# 5_-USB2_TYPEC_USIC.net
KiCad netlist of a schematic drawn in Altium Designer
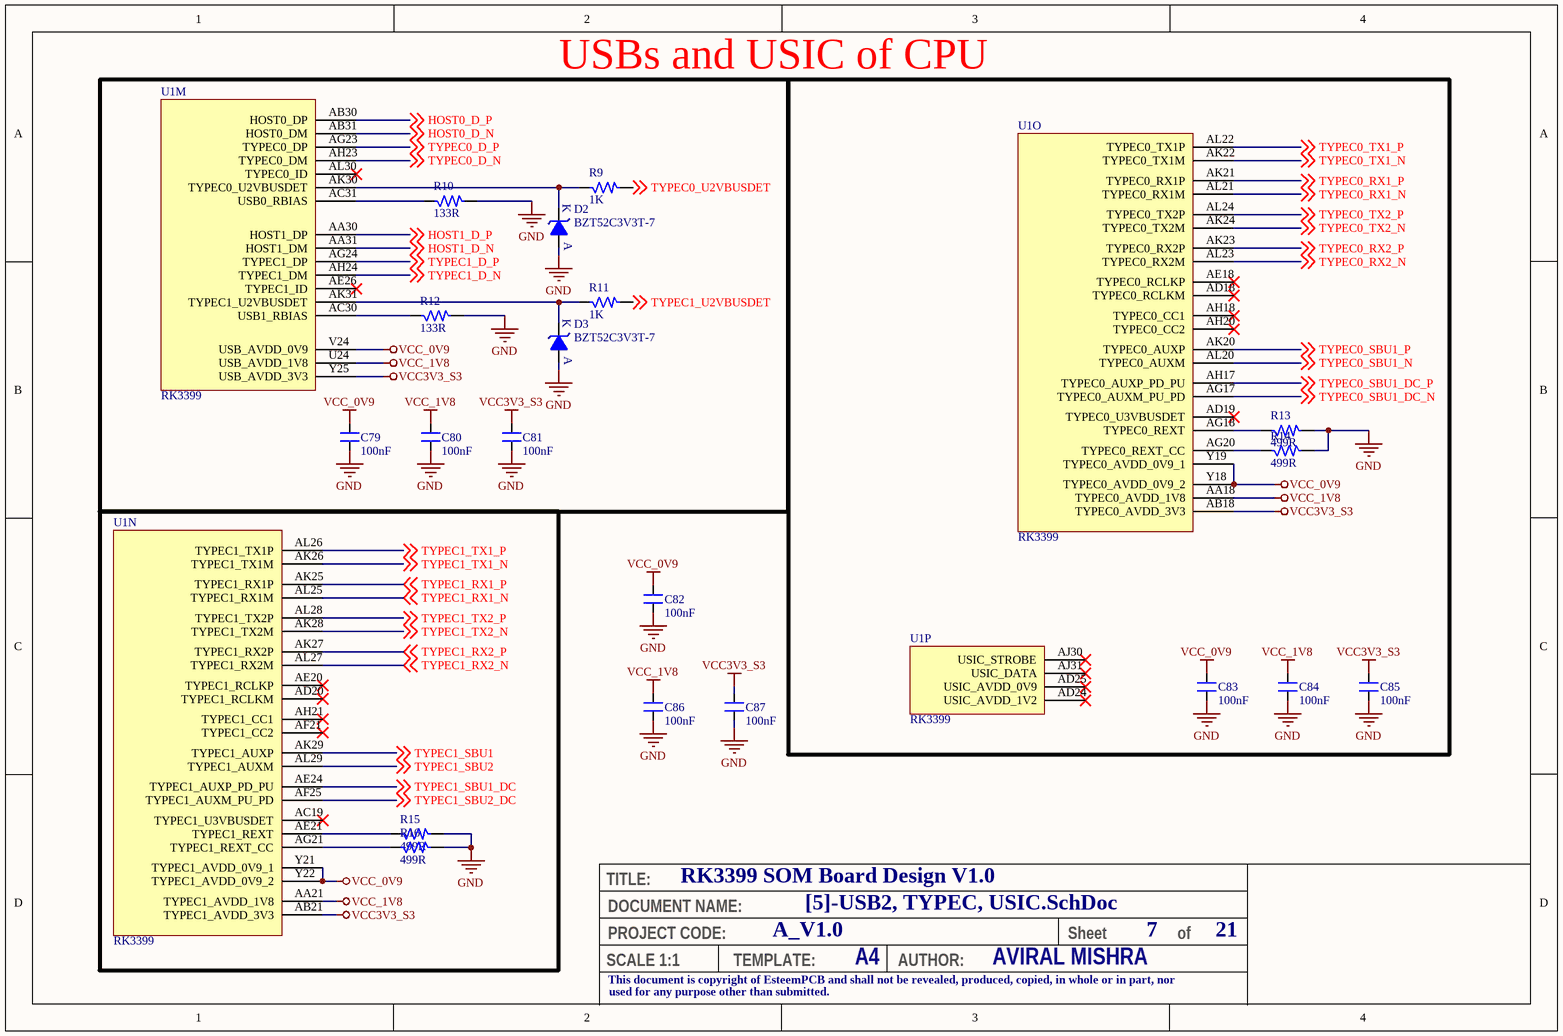
[diagram p0: [5]-USB2, TYPEC, USIC.SchDoc]

(export (version "E")
  (design (tool "Eeschema 10.0.6"))
  (components
    (comp (ref "C79")
      (value "100nF")
      (footprint "CAP_0201")
      (description "0.1µF ±10% 25V Ceramic Capacitor X5R 0201 (0603 Metric)")
      (fields
        (field (name "MANUFACTURER") "TDK Corporation")
        (field (name "MANUFACTURER PART NUMBER") "C0603X5R1E104K030BB")
      )
      (libsource (lib "RK3399 _Module_Intlib") (part "CAP_100nF-25V-10%-0201"))
    )
    (comp (ref "C80")
      (value "100nF")
      (footprint "CAP_0201")
      (description "0.1µF ±10% 25V Ceramic Capacitor X5R 0201 (0603 Metric)")
      (fields
        (field (name "MANUFACTURER") "TDK Corporation")
        (field (name "MANUFACTURER PART NUMBER") "C0603X5R1E104K030BB")
      )
      (libsource (lib "RK3399 _Module_Intlib") (part "CAP_100nF-25V-10%-0201"))
    )
    (comp (ref "C81")
      (value "100nF")
      (footprint "CAP_0201")
      (description "0.1µF ±10% 25V Ceramic Capacitor X5R 0201 (0603 Metric)")
      (fields
        (field (name "MANUFACTURER") "TDK Corporation")
        (field (name "MANUFACTURER PART NUMBER") "C0603X5R1E104K030BB")
      )
      (libsource (lib "RK3399 _Module_Intlib") (part "CAP_100nF-25V-10%-0201"))
    )
    (comp (ref "C82")
      (value "100nF")
      (footprint "CAP_0201")
      (description "0.1µF ±10% 25V Ceramic Capacitor X5R 0201 (0603 Metric)")
      (fields
        (field (name "MANUFACTURER") "TDK Corporation")
        (field (name "MANUFACTURER PART NUMBER") "C0603X5R1E104K030BB")
      )
      (libsource (lib "RK3399 _Module_Intlib") (part "CAP_100nF-25V-10%-0201"))
    )
    (comp (ref "C83")
      (value "100nF")
      (footprint "CAP_0201")
      (description "0.1µF ±10% 25V Ceramic Capacitor X5R 0201 (0603 Metric)")
      (fields
        (field (name "MANUFACTURER") "TDK Corporation")
        (field (name "MANUFACTURER PART NUMBER") "C0603X5R1E104K030BB")
      )
      (libsource (lib "RK3399 _Module_Intlib") (part "CAP_100nF-25V-10%-0201"))
    )
    (comp (ref "C84")
      (value "100nF")
      (footprint "CAP_0201")
      (description "0.1µF ±10% 25V Ceramic Capacitor X5R 0201 (0603 Metric)")
      (fields
        (field (name "MANUFACTURER") "TDK Corporation")
        (field (name "MANUFACTURER PART NUMBER") "C0603X5R1E104K030BB")
      )
      (libsource (lib "RK3399 _Module_Intlib") (part "CAP_100nF-25V-10%-0201"))
    )
    (comp (ref "C85")
      (value "100nF")
      (footprint "CAP_0201")
      (description "0.1µF ±10% 25V Ceramic Capacitor X5R 0201 (0603 Metric)")
      (fields
        (field (name "MANUFACTURER") "TDK Corporation")
        (field (name "MANUFACTURER PART NUMBER") "C0603X5R1E104K030BB")
      )
      (libsource (lib "RK3399 _Module_Intlib") (part "CAP_100nF-25V-10%-0201"))
    )
    (comp (ref "C86")
      (value "100nF")
      (footprint "CAP_0201")
      (description "0.1µF ±10% 25V Ceramic Capacitor X5R 0201 (0603 Metric)")
      (fields
        (field (name "MANUFACTURER") "TDK Corporation")
        (field (name "MANUFACTURER PART NUMBER") "C0603X5R1E104K030BB")
      )
      (libsource (lib "RK3399 _Module_Intlib") (part "CAP_100nF-25V-10%-0201"))
    )
    (comp (ref "C87")
      (value "100nF")
      (footprint "CAP_0201")
      (description "0.1µF ±10% 25V Ceramic Capacitor X5R 0201 (0603 Metric)")
      (fields
        (field (name "MANUFACTURER") "TDK Corporation")
        (field (name "MANUFACTURER PART NUMBER") "C0603X5R1E104K030BB")
      )
      (libsource (lib "RK3399 _Module_Intlib") (part "CAP_100nF-25V-10%-0201"))
    )
    (comp (ref "D2")
      (value "BZT52C3V3T-7")
      (footprint "DIO_SOD523")
      (description "Zener Diode 3.3V 300mW ±6% Surface Mount SOD-523")
      (fields (field (name "MANUFACTURER") "Diodes Incorporated"))
      (libsource (lib "RK3399 _Module_Schlib") (part "DIO-Z_3.3V-300mW-SOD-523"))
    )
    (comp (ref "D3")
      (value "BZT52C3V3T-7")
      (footprint "DIO_SOD523")
      (description "Zener Diode 3.3V 300mW ±6% Surface Mount SOD-523")
      (fields (field (name "MANUFACTURER") "Diodes Incorporated"))
      (libsource (lib "RK3399 _Module_Schlib") (part "DIO-Z_3.3V-300mW-SOD-523"))
    )
    (comp (ref "R9")
      (value "1K")
      (footprint "RES_0201")
      (description "1 kOhms ±1% 0.05W, 1/20W Chip Resistor 0201 (0603 Metric) Thick Film")
      (fields
        (field (name "MANUFACTURER") "Yageo")
        (field (name "MANUFACTURER PART NUMBER") "RC0201FR-071KL")
      )
      (libsource (lib "RK3399 _Module_Intlib") (part "RES_1K-0.05W-1%-0201"))
    )
    (comp (ref "R10")
      (value "133R")
      (footprint "RES_0201")
      (description "133 Ohms ±1% 0.05W, 1/20W Chip Resistor 0201 (0603 Metric) Automotive AEC-Q200 Thick Film")
      (fields
        (field (name "MANUFACTURER") "Panasonic Electronic Components")
        (field (name "MANUFACTURER PART NUMBER") "ERJ-1GNF1330C")
      )
      (libsource (lib "RK3399 _Module_Intlib") (part "RES_133R-0.05W-1%-0201"))
    )
    (comp (ref "R11")
      (value "1K")
      (footprint "RES_0201")
      (description "1 kOhms ±1% 0.05W, 1/20W Chip Resistor 0201 (0603 Metric) Thick Film")
      (fields
        (field (name "MANUFACTURER") "Yageo")
        (field (name "MANUFACTURER PART NUMBER") "RC0201FR-071KL")
      )
      (libsource (lib "RK3399 _Module_Intlib") (part "RES_1K-0.05W-1%-0201"))
    )
    (comp (ref "R12")
      (value "133R")
      (footprint "RES_0201")
      (description "133 Ohms ±1% 0.05W, 1/20W Chip Resistor 0201 (0603 Metric) Automotive AEC-Q200 Thick Film")
      (fields
        (field (name "MANUFACTURER") "Panasonic Electronic Components")
        (field (name "MANUFACTURER PART NUMBER") "ERJ-1GNF1330C")
      )
      (libsource (lib "RK3399 _Module_Intlib") (part "RES_133R-0.05W-1%-0201"))
    )
    (comp (ref "R13")
      (value "499R")
      (footprint "RES_0201")
      (description "499 Ohms ±1% 0.05W, 1/20W Chip Resistor 0201 (0603 Metric) Thick Film")
      (fields
        (field (name "MANUFACTURER") "Stackpole Electronics Inc")
        (field (name "MANUFACTURER PART NUMBER") "RMCF0201FT499R")
      )
      (libsource (lib "RK3399 _Module_Intlib") (part "RES_499R-0.05W-1%-0201"))
    )
    (comp (ref "R14")
      (value "499R")
      (footprint "RES_0201")
      (description "499 Ohms ±1% 0.05W, 1/20W Chip Resistor 0201 (0603 Metric) Thick Film")
      (fields
        (field (name "MANUFACTURER") "Stackpole Electronics Inc")
        (field (name "MANUFACTURER PART NUMBER") "RMCF0201FT499R")
      )
      (libsource (lib "RK3399 _Module_Intlib") (part "RES_499R-0.05W-1%-0201"))
    )
    (comp (ref "R15")
      (value "499R")
      (footprint "RES_0201")
      (description "499 Ohms ±1% 0.05W, 1/20W Chip Resistor 0201 (0603 Metric) Thick Film")
      (fields
        (field (name "MANUFACTURER") "Stackpole Electronics Inc")
        (field (name "MANUFACTURER PART NUMBER") "RMCF0201FT499R")
      )
      (libsource (lib "RK3399 _Module_Intlib") (part "RES_499R-0.05W-1%-0201"))
    )
    (comp (ref "R16")
      (value "499R")
      (footprint "RES_0201")
      (description "499 Ohms ±1% 0.05W, 1/20W Chip Resistor 0201 (0603 Metric) Thick Film")
      (fields
        (field (name "MANUFACTURER") "Stackpole Electronics Inc")
        (field (name "MANUFACTURER PART NUMBER") "RMCF0201FT499R")
      )
      (libsource (lib "RK3399 _Module_Intlib") (part "RES_499R-0.05W-1%-0201"))
    )
    (comp (ref "U1")
      (value "RK3399")
      (footprint "FBGA828_23_826X826")
      (description "RK3399 is a low power, high performance processor for computing, personal mobile.")
      (fields (field (name "MANUFACTURER") "Rockchip"))
      (libsource (lib "RK3399 _Module_Schlib") (part "IC_RK3399-FCBGA828"))
    )
  )
  (nets
    (net (code "1") (name "GND") (class "Default")
      (node (ref "C79") (pin "2") (pinfunction "2_2") (pintype "passive"))
      (node (ref "C80") (pin "1") (pinfunction "1_1") (pintype "passive"))
      (node (ref "C81") (pin "1") (pinfunction "1_1") (pintype "passive"))
      (node (ref "C82") (pin "1") (pinfunction "1_1") (pintype "passive"))
      (node (ref "C83") (pin "1") (pinfunction "1_1") (pintype "passive"))
      (node (ref "C84") (pin "1") (pinfunction "1_1") (pintype "passive"))
      (node (ref "C85") (pin "1") (pinfunction "1_1") (pintype "passive"))
      (node (ref "C86") (pin "1") (pinfunction "1_1") (pintype "passive"))
      (node (ref "C87") (pin "1") (pinfunction "1_1") (pintype "passive"))
      (node (ref "D2") (pin "A") (pinfunction "A_A") (pintype "passive"))
      (node (ref "D3") (pin "A") (pinfunction "A_A") (pintype "passive"))
      (node (ref "R10") (pin "2") (pinfunction "2_2") (pintype "passive"))
      (node (ref "R12") (pin "2") (pinfunction "2_2") (pintype "passive"))
      (node (ref "R13") (pin "2") (pinfunction "2_2") (pintype "passive"))
      (node (ref "R14") (pin "2") (pinfunction "2_2") (pintype "passive"))
      (node (ref "R15") (pin "2") (pinfunction "2_2") (pintype "passive"))
      (node (ref "R16") (pin "2") (pinfunction "2_2") (pintype "passive"))
    )
    (net (code "2") (name "HOST0_D_N") (class "Default")
      (node (ref "U1") (pin "AB31") (pinfunction "HOST0_DM_AB31") (pintype "passive"))
    )
    (net (code "3") (name "HOST0_D_P") (class "Default")
      (node (ref "U1") (pin "AB30") (pinfunction "HOST0_DP_AB30") (pintype "passive"))
    )
    (net (code "4") (name "HOST1_D_N") (class "Default")
      (node (ref "U1") (pin "AA31") (pinfunction "HOST1_DM_AA31") (pintype "passive"))
    )
    (net (code "5") (name "HOST1_D_P") (class "Default")
      (node (ref "U1") (pin "AA30") (pinfunction "HOST1_DP_AA30") (pintype "passive"))
    )
    (net (code "6") (name "Net-(U1M-TYPEC0_U2VBUSDET)") (class "Default")
      (node (ref "D2") (pin "K") (pinfunction "K_K") (pintype "passive"))
      (node (ref "R9") (pin "1") (pinfunction "1_1") (pintype "passive"))
      (node (ref "U1") (pin "AK30") (pinfunction "TYPEC0_U2VBUSDET_AK30") (pintype "passive"))
    )
    (net (code "7") (name "Net-(U1M-TYPEC1_U2VBUSDET)") (class "Default")
      (node (ref "D3") (pin "K") (pinfunction "K_K") (pintype "passive"))
      (node (ref "R11") (pin "1") (pinfunction "1_1") (pintype "passive"))
      (node (ref "U1") (pin "AK31") (pinfunction "TYPEC1_U2VBUSDET_AK31") (pintype "passive"))
    )
    (net (code "8") (name "Net-(U1M-USB0_RBIAS)") (class "Default")
      (node (ref "R10") (pin "1") (pinfunction "1_1") (pintype "passive"))
      (node (ref "U1") (pin "AC31") (pinfunction "USB0_RBIAS_AC31") (pintype "passive"))
    )
    (net (code "9") (name "Net-(U1M-USB1_RBIAS)") (class "Default")
      (node (ref "R12") (pin "1") (pinfunction "1_1") (pintype "passive"))
      (node (ref "U1") (pin "AC30") (pinfunction "USB1_RBIAS_AC30") (pintype "passive"))
    )
    (net (code "10") (name "Net-(U1N-TYPEC1_REXT)") (class "Default")
      (node (ref "R15") (pin "1") (pinfunction "1_1") (pintype "passive"))
      (node (ref "U1") (pin "AE21") (pinfunction "TYPEC1_REXT_AE21") (pintype "passive"))
    )
    (net (code "11") (name "Net-(U1N-TYPEC1_REXT_CC)") (class "Default")
      (node (ref "R16") (pin "1") (pinfunction "1_1") (pintype "passive"))
      (node (ref "U1") (pin "AG21") (pinfunction "TYPEC1_REXT_CC_AG21") (pintype "passive"))
    )
    (net (code "12") (name "Net-(U1O-TYPEC0_REXT)") (class "Default")
      (node (ref "R13") (pin "1") (pinfunction "1_1") (pintype "passive"))
      (node (ref "U1") (pin "AG18") (pinfunction "TYPEC0_REXT_AG18") (pintype "passive"))
    )
    (net (code "13") (name "Net-(U1O-TYPEC0_REXT_CC)") (class "Default")
      (node (ref "R14") (pin "1") (pinfunction "1_1") (pintype "passive"))
      (node (ref "U1") (pin "AG20") (pinfunction "TYPEC0_REXT_CC_AG20") (pintype "passive"))
    )
    (net (code "14") (name "TYPEC0_D_N") (class "Default")
      (node (ref "U1") (pin "AH23") (pinfunction "TYPEC0_DM_AH23") (pintype "passive"))
    )
    (net (code "15") (name "TYPEC0_D_P") (class "Default")
      (node (ref "U1") (pin "AG23") (pinfunction "TYPEC0_DP_AG23") (pintype "passive"))
    )
    (net (code "16") (name "TYPEC0_RX1_N") (class "Default")
      (node (ref "U1") (pin "AL21") (pinfunction "TYPEC0_RX1M_AL21") (pintype "passive"))
    )
    (net (code "17") (name "TYPEC0_RX1_P") (class "Default")
      (node (ref "U1") (pin "AK21") (pinfunction "TYPEC0_RX1P_AK21") (pintype "passive"))
    )
    (net (code "18") (name "TYPEC0_RX2_N") (class "Default")
      (node (ref "U1") (pin "AL23") (pinfunction "TYPEC0_RX2M_AL23") (pintype "passive"))
    )
    (net (code "19") (name "TYPEC0_RX2_P") (class "Default")
      (node (ref "U1") (pin "AK23") (pinfunction "TYPEC0_RX2P_AK23") (pintype "passive"))
    )
    (net (code "20") (name "TYPEC0_SBU1_DC_N") (class "Default")
      (node (ref "U1") (pin "AG17") (pinfunction "TYPEC0_AUXM_PU_PD_AG17") (pintype "passive"))
    )
    (net (code "21") (name "TYPEC0_SBU1_DC_P") (class "Default")
      (node (ref "U1") (pin "AH17") (pinfunction "TYPEC0_AUXP_PD_PU_AH17") (pintype "passive"))
    )
    (net (code "22") (name "TYPEC0_SBU1_N") (class "Default")
      (node (ref "U1") (pin "AL20") (pinfunction "TYPEC0_AUXM_AL20") (pintype "passive"))
    )
    (net (code "23") (name "TYPEC0_SBU1_P") (class "Default")
      (node (ref "U1") (pin "AK20") (pinfunction "TYPEC0_AUXP_AK20") (pintype "passive"))
    )
    (net (code "24") (name "TYPEC0_TX1_N") (class "Default")
      (node (ref "U1") (pin "AK22") (pinfunction "TYPEC0_TX1M_AK22") (pintype "passive"))
    )
    (net (code "25") (name "TYPEC0_TX1_P") (class "Default")
      (node (ref "U1") (pin "AL22") (pinfunction "TYPEC0_TX1P_AL22") (pintype "passive"))
    )
    (net (code "26") (name "TYPEC0_TX2_N") (class "Default")
      (node (ref "U1") (pin "AK24") (pinfunction "TYPEC0_TX2M_AK24") (pintype "passive"))
    )
    (net (code "27") (name "TYPEC0_TX2_P") (class "Default")
      (node (ref "U1") (pin "AL24") (pinfunction "TYPEC0_TX2P_AL24") (pintype "passive"))
    )
    (net (code "28") (name "TYPEC0_U2VBUSDET") (class "Default")
      (node (ref "R9") (pin "2") (pinfunction "2_2") (pintype "passive"))
    )
    (net (code "29") (name "TYPEC1_D_N") (class "Default")
      (node (ref "U1") (pin "AH24") (pinfunction "TYPEC1_DM_AH24") (pintype "passive"))
    )
    (net (code "30") (name "TYPEC1_D_P") (class "Default")
      (node (ref "U1") (pin "AG24") (pinfunction "TYPEC1_DP_AG24") (pintype "passive"))
    )
    (net (code "31") (name "TYPEC1_RX1_N") (class "Default")
      (node (ref "U1") (pin "AL25") (pinfunction "TYPEC1_RX1M_AL25") (pintype "passive"))
    )
    (net (code "32") (name "TYPEC1_RX1_P") (class "Default")
      (node (ref "U1") (pin "AK25") (pinfunction "TYPEC1_RX1P_AK25") (pintype "passive"))
    )
    (net (code "33") (name "TYPEC1_RX2_N") (class "Default")
      (node (ref "U1") (pin "AL27") (pinfunction "TYPEC1_RX2M_AL27") (pintype "passive"))
    )
    (net (code "34") (name "TYPEC1_RX2_P") (class "Default")
      (node (ref "U1") (pin "AK27") (pinfunction "TYPEC1_RX2P_AK27") (pintype "passive"))
    )
    (net (code "35") (name "TYPEC1_SBU1") (class "Default")
      (node (ref "U1") (pin "AK29") (pinfunction "TYPEC1_AUXP_AK29") (pintype "passive"))
    )
    (net (code "36") (name "TYPEC1_SBU1_DC") (class "Default")
      (node (ref "U1") (pin "AE24") (pinfunction "TYPEC1_AUXP_PD_PU_AE24") (pintype "passive"))
    )
    (net (code "37") (name "TYPEC1_SBU2") (class "Default")
      (node (ref "U1") (pin "AL29") (pinfunction "TYPEC1_AUXM_AL29") (pintype "passive"))
    )
    (net (code "38") (name "TYPEC1_SBU2_DC") (class "Default")
      (node (ref "U1") (pin "AF25") (pinfunction "TYPEC1_AUXM_PU_PD_AF25") (pintype "passive"))
    )
    (net (code "39") (name "TYPEC1_TX1_N") (class "Default")
      (node (ref "U1") (pin "AK26") (pinfunction "TYPEC1_TX1M_AK26") (pintype "passive"))
    )
    (net (code "40") (name "TYPEC1_TX1_P") (class "Default")
      (node (ref "U1") (pin "AL26") (pinfunction "TYPEC1_TX1P_AL26") (pintype "passive"))
    )
    (net (code "41") (name "TYPEC1_TX2_N") (class "Default")
      (node (ref "U1") (pin "AK28") (pinfunction "TYPEC1_TX2M_AK28") (pintype "passive"))
    )
    (net (code "42") (name "TYPEC1_TX2_P") (class "Default")
      (node (ref "U1") (pin "AL28") (pinfunction "TYPEC1_TX2P_AL28") (pintype "passive"))
    )
    (net (code "43") (name "TYPEC1_U2VBUSDET") (class "Default")
      (node (ref "R11") (pin "2") (pinfunction "2_2") (pintype "passive"))
    )
    (net (code "44") (name "VCC3V3_S3") (class "Default")
      (node (ref "C81") (pin "2") (pinfunction "2_2") (pintype "passive"))
      (node (ref "C85") (pin "2") (pinfunction "2_2") (pintype "passive"))
      (node (ref "C87") (pin "2") (pinfunction "2_2") (pintype "passive"))
      (node (ref "U1") (pin "AB18") (pinfunction "TYPEC0_AVDD_3V3_AB18") (pintype "passive"))
      (node (ref "U1") (pin "AB21") (pinfunction "TYPEC1_AVDD_3V3_AB21") (pintype "passive"))
      (node (ref "U1") (pin "Y25") (pinfunction "USB_AVDD_3V3_Y25") (pintype "passive"))
    )
    (net (code "45") (name "VCC_0V9") (class "Default")
      (node (ref "C79") (pin "1") (pinfunction "1_1") (pintype "passive"))
      (node (ref "C82") (pin "2") (pinfunction "2_2") (pintype "passive"))
      (node (ref "C83") (pin "2") (pinfunction "2_2") (pintype "passive"))
      (node (ref "U1") (pin "V24") (pinfunction "USB_AVDD_0V9_V24") (pintype "passive"))
      (node (ref "U1") (pin "Y18") (pinfunction "TYPEC0_AVDD_0V9_2_Y18") (pintype "passive"))
      (node (ref "U1") (pin "Y19") (pinfunction "TYPEC0_AVDD_0V9_1_Y19") (pintype "passive"))
      (node (ref "U1") (pin "Y21") (pinfunction "TYPEC1_AVDD_0V9_1_Y21") (pintype "passive"))
      (node (ref "U1") (pin "Y22") (pinfunction "TYPEC1_AVDD_0V9_2_Y22") (pintype "passive"))
    )
    (net (code "46") (name "VCC_1V8") (class "Default")
      (node (ref "C80") (pin "2") (pinfunction "2_2") (pintype "passive"))
      (node (ref "C84") (pin "2") (pinfunction "2_2") (pintype "passive"))
      (node (ref "C86") (pin "2") (pinfunction "2_2") (pintype "passive"))
      (node (ref "U1") (pin "AA18") (pinfunction "TYPEC0_AVDD_1V8_AA18") (pintype "passive"))
      (node (ref "U1") (pin "AA21") (pinfunction "TYPEC1_AVDD_1V8_AA21") (pintype "passive"))
      (node (ref "U1") (pin "U24") (pinfunction "USB_AVDD_1V8_U24") (pintype "passive"))
    )
    (net (code "47") (name "unconnected-(U1M-TYPEC0_ID-PadAL30)") (class "Default")
      (node (ref "U1") (pin "AL30") (pinfunction "TYPEC0_ID_AL30") (pintype "passive+no_connect"))
    )
    (net (code "48") (name "unconnected-(U1M-TYPEC1_ID-PadAE26)") (class "Default")
      (node (ref "U1") (pin "AE26") (pinfunction "TYPEC1_ID_AE26") (pintype "passive+no_connect"))
    )
    (net (code "49") (name "unconnected-(U1N-TYPEC1_CC1-PadAH21)") (class "Default")
      (node (ref "U1") (pin "AH21") (pinfunction "TYPEC1_CC1_AH21") (pintype "passive+no_connect"))
    )
    (net (code "50") (name "unconnected-(U1N-TYPEC1_CC2-PadAF21)") (class "Default")
      (node (ref "U1") (pin "AF21") (pinfunction "TYPEC1_CC2_AF21") (pintype "passive+no_connect"))
    )
    (net (code "51") (name "unconnected-(U1N-TYPEC1_RCLKM-PadAD20)") (class "Default")
      (node (ref "U1") (pin "AD20") (pinfunction "TYPEC1_RCLKM_AD20") (pintype "passive+no_connect"))
    )
    (net (code "52") (name "unconnected-(U1N-TYPEC1_RCLKP-PadAE20)") (class "Default")
      (node (ref "U1") (pin "AE20") (pinfunction "TYPEC1_RCLKP_AE20") (pintype "passive+no_connect"))
    )
    (net (code "53") (name "unconnected-(U1N-TYPEC1_U3VBUSDET-PadAC19)") (class "Default")
      (node (ref "U1") (pin "AC19") (pinfunction "TYPEC1_U3VBUSDET_AC19") (pintype "passive+no_connect"))
    )
    (net (code "54") (name "unconnected-(U1O-TYPEC0_CC1-PadAH18)") (class "Default")
      (node (ref "U1") (pin "AH18") (pinfunction "TYPEC0_CC1_AH18") (pintype "passive+no_connect"))
    )
    (net (code "55") (name "unconnected-(U1O-TYPEC0_CC2-PadAH20)") (class "Default")
      (node (ref "U1") (pin "AH20") (pinfunction "TYPEC0_CC2_AH20") (pintype "passive+no_connect"))
    )
    (net (code "56") (name "unconnected-(U1O-TYPEC0_RCLKM-PadAD18)") (class "Default")
      (node (ref "U1") (pin "AD18") (pinfunction "TYPEC0_RCLKM_AD18") (pintype "passive+no_connect"))
    )
    (net (code "57") (name "unconnected-(U1O-TYPEC0_RCLKP-PadAE18)") (class "Default")
      (node (ref "U1") (pin "AE18") (pinfunction "TYPEC0_RCLKP_AE18") (pintype "passive+no_connect"))
    )
    (net (code "58") (name "unconnected-(U1O-TYPEC0_U3VBUSDET-PadAD19)") (class "Default")
      (node (ref "U1") (pin "AD19") (pinfunction "TYPEC0_U3VBUSDET_AD19") (pintype "passive+no_connect"))
    )
    (net (code "59") (name "unconnected-(U1P-USIC_AVDD_0V9-PadAD25)") (class "Default")
      (node (ref "U1") (pin "AD25") (pinfunction "USIC_AVDD_0V9_AD25") (pintype "passive+no_connect"))
    )
    (net (code "60") (name "unconnected-(U1P-USIC_AVDD_1V2-PadAD24)") (class "Default")
      (node (ref "U1") (pin "AD24") (pinfunction "USIC_AVDD_1V2_AD24") (pintype "passive+no_connect"))
    )
    (net (code "61") (name "unconnected-(U1P-USIC_DATA-PadAJ31)") (class "Default")
      (node (ref "U1") (pin "AJ31") (pinfunction "USIC_DATA_AJ31") (pintype "passive+no_connect"))
    )
    (net (code "62") (name "unconnected-(U1P-USIC_STROBE-PadAJ30)") (class "Default")
      (node (ref "U1") (pin "AJ30") (pinfunction "USIC_STROBE_AJ30") (pintype "passive+no_connect"))
    )
  )
)
